# indicator_light.net
KiCad netlist of a schematic drawn in Altium Designer
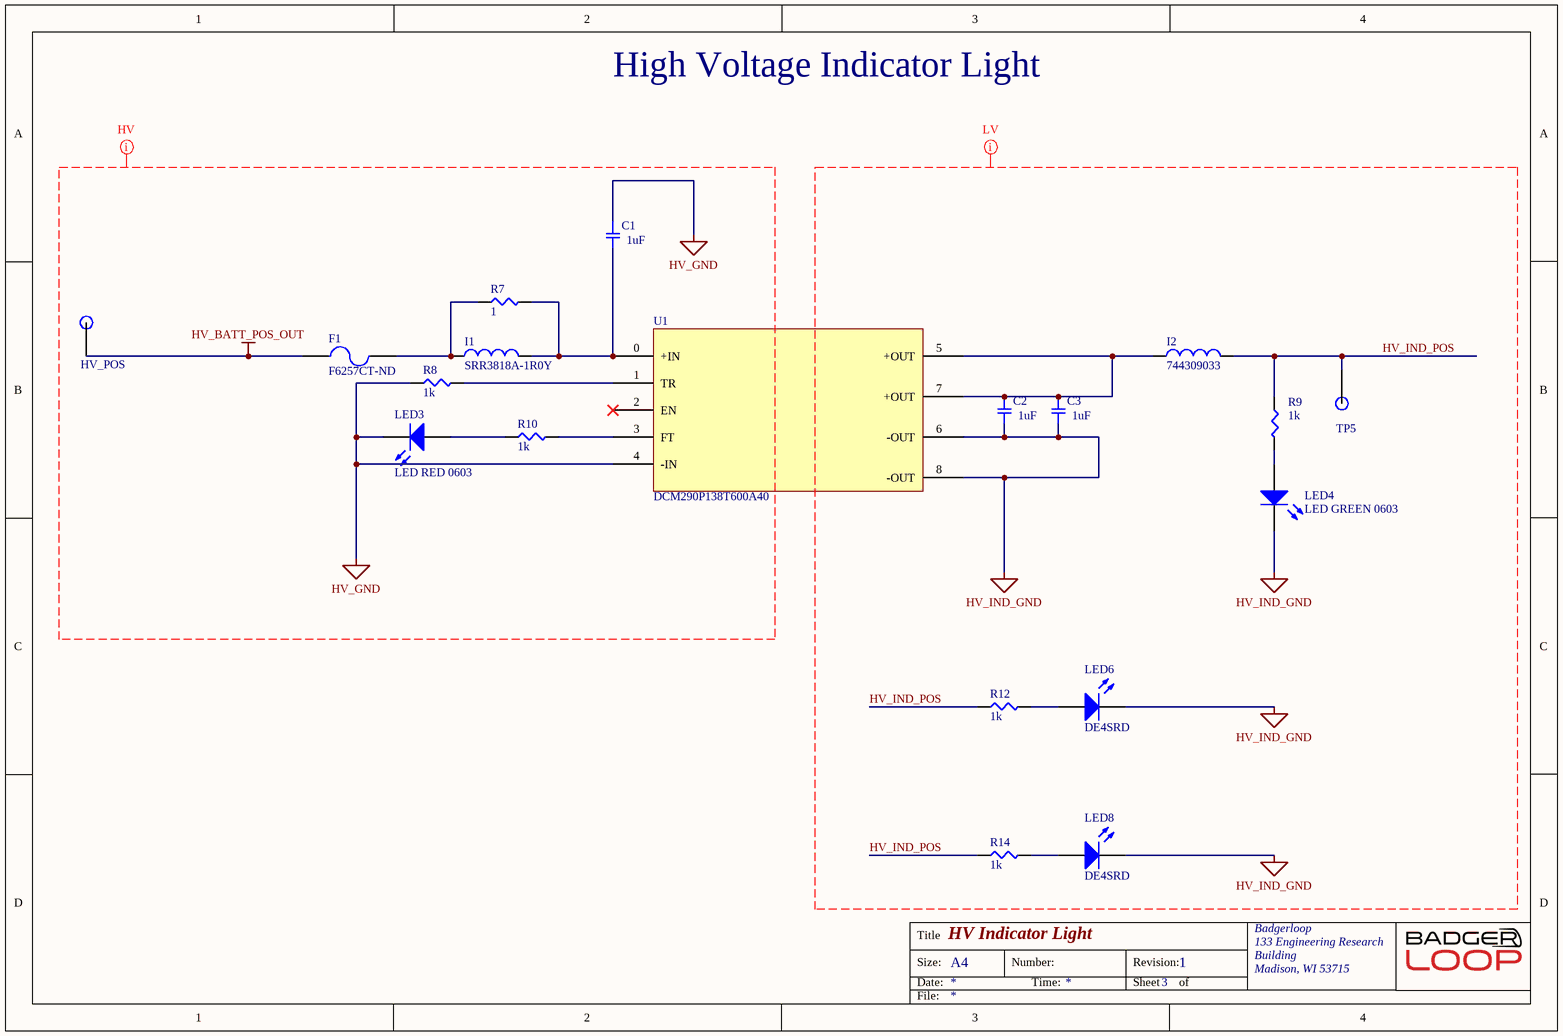
[diagram p0: indicator_light.SchDoc]

(export (version "E")
  (design (tool "Eeschema 10.0.6"))
  (components
    (comp (ref "C1")
      (value "CGA9P4X7T2W105K250KE_1")
      (footprint "CAPC5860X28N")
      (description "CAP CER 1UF 450V X7T 2220")
      (fields
        (field (name "MANUFACTURER") "TDK")
        (field (name "MANUFACTURER PART NUMBER") "CGA9P4X7T2W105K250KE")
        (field (name "CAPACITANCE") "1uF")
      )
      (libsource (lib "altium-import") (part "root_0_CGA9P4X7T2W105K250KE_1_"))
    )
    (comp (ref "C2")
      (value "CGA9P4X7T2W105K250KE_1")
      (footprint "CAPC5860X28N")
      (description "CAP CER 1UF 450V X7T 2220")
      (fields
        (field (name "MANUFACTURER") "TDK")
        (field (name "MANUFACTURER PART NUMBER") "CGA9P4X7T2W105K250KE")
        (field (name "CAPACITANCE") "1uF")
      )
      (libsource (lib "altium-import") (part "root_0_CGA9P4X7T2W105K250KE_1_"))
    )
    (comp (ref "C3")
      (value "CGA9P4X7T2W105K250KE_1")
      (footprint "CAPC5860X28N")
      (description "CAP CER 1UF 450V X7T 2220")
      (fields
        (field (name "MANUFACTURER") "TDK")
        (field (name "MANUFACTURER PART NUMBER") "CGA9P4X7T2W105K250KE")
        (field (name "CAPACITANCE") "1uF")
      )
      (libsource (lib "altium-import") (part "root_0_CGA9P4X7T2W105K250KE_1_"))
    )
    (comp (ref "F1")
      (value "F6257CT-ND")
      (footprint "FUSE BOARD MNT 500MA 350VAC/VDC")
      (description "FUSE BOARD MNT 500MA 350VAC/VDC")
      (fields (field (name "MANUFACTURER") "Littelfuse"))
      (libsource (lib "misc") (part "F6257CT-ND"))
    )
    (comp (ref "HV_POS")
      (value "TP")
      (footprint "Test Point")
      (description "SMD TEST POINT")
      (libsource (lib "misc") (part "TP"))
    )
    (comp (ref "I1")
      (value "SRR3818A-1R0Y")
      (footprint "INDM3838X18N")
      (description "FIXED IND 1UH 3.6A 37 MOHM SMD")
      (fields (field (name "MANUFACTURER") "Bourns Inc."))
      (libsource (lib "misc") (part "SRR3818A-1R0Y"))
    )
    (comp (ref "I2")
      (value "744309033")
      (footprint "INDM140130X90N")
      (description "FIXED IND 330NH 47.5A 0.165 MOHM")
      (fields (field (name "MANUFACTURER") "Wurth"))
      (libsource (lib "misc") (part "744309033"))
    )
    (comp (ref "LED3")
      (value "LED RED 0603")
      (footprint "LED 0603 RED")
      (description "Red 631nm LED Indication - Discrete 2V 0603 (1608 Metric)")
      (fields (field (name "MANUFACTURER") "Lite-On Inc."))
      (libsource (lib "misc") (part "LED RED 0603"))
    )
    (comp (ref "LED4")
      (value "LED GREEN 0603")
      (footprint "LED 0603 GREEN")
      (fields (field (name "MANUFACTURER") "Lite-On Inc."))
      (libsource (lib "misc") (part "LED GREEN 0603"))
    )
    (comp (ref "LED6")
      (value "DE4SRD")
      (footprint "DE4SRD")
      (description "LED Bars and Arrays Red 640nm 300mcd Diffused Light Bar")
      (fields (field (name "MANUFACTURER") "Kingbright"))
      (libsource (lib "shelby_temp") (part "DE4SRD"))
    )
    (comp (ref "LED8")
      (value "DE4SRD")
      (footprint "DE4SRD")
      (description "LED Bars and Arrays Red 640nm 300mcd Diffused Light Bar")
      (fields (field (name "MANUFACTURER") "Kingbright"))
      (libsource (lib "shelby_temp") (part "DE4SRD"))
    )
    (comp (ref "R7")
      (value "1")
      (footprint "SMD-0805-RES")
      (description "RES SMD 1 OHM 5% 1/3W 0805")
      (fields (field (name "PART NUMBER") "ERJ-6BQJ1R0V") (field (name "DIGI-KEY PART NUMBER") "P17527CT-ND"))
      (libsource (lib "resistors") (part "ERJ-6BQJ1R0V"))
    )
    (comp (ref "R8")
      (value "1k")
      (footprint "SMD-0805-RES")
      (description "RES SMD 1K OHM 1% 1/8W 0805")
      (fields
        (field (name "PART NUMBER") "ERJ-6ENF1001V")
        (field (name "DIGI-KEY PART NUMBER") "P1.00KCCT-ND")
      )
      (libsource (lib "resistors") (part "ERJ-6ENF1001V"))
    )
    (comp (ref "R9")
      (value "1k")
      (footprint "SMD-0805-RES")
      (description "RES SMD 1K OHM 1% 1/8W 0805")
      (fields
        (field (name "PART NUMBER") "ERJ-6ENF1001V")
        (field (name "DIGI-KEY PART NUMBER") "P1.00KCCT-ND")
      )
      (libsource (lib "resistors") (part "ERJ-6ENF1001V"))
    )
    (comp (ref "R10")
      (value "1k")
      (footprint "SMD-0805-RES")
      (description "RES SMD 1K OHM 1% 1/8W 0805")
      (fields
        (field (name "PART NUMBER") "ERJ-6ENF1001V")
        (field (name "DIGI-KEY PART NUMBER") "P1.00KCCT-ND")
      )
      (libsource (lib "resistors") (part "ERJ-6ENF1001V"))
    )
    (comp (ref "R12")
      (value "1k")
      (footprint "SMD-0805-RES")
      (description "RES SMD 1K OHM 1% 1/8W 0805")
      (fields
        (field (name "PART NUMBER") "ERJ-6ENF1001V")
        (field (name "DIGI-KEY PART NUMBER") "P1.00KCCT-ND")
      )
      (libsource (lib "resistors") (part "ERJ-6ENF1001V"))
    )
    (comp (ref "R14")
      (value "1k")
      (footprint "SMD-0805-RES")
      (description "RES SMD 1K OHM 1% 1/8W 0805")
      (fields
        (field (name "PART NUMBER") "ERJ-6ENF1001V")
        (field (name "DIGI-KEY PART NUMBER") "P1.00KCCT-ND")
      )
      (libsource (lib "resistors") (part "ERJ-6ENF1001V"))
    )
    (comp (ref "TP5")
      (value "TP")
      (footprint "Test Point")
      (description "SMD TEST POINT")
      (libsource (lib "misc") (part "TP"))
    )
    (comp (ref "U1")
      (value "DCM290P138T600A40")
      (footprint "DCM290y138x600A40")
      (description "DC DC CONVERTER 13.8V 600W")
      (fields (field (name "MANUFACTURER") "Vicor"))
      (libsource (lib "ic") (part "DCM290P138T600A40"))
    )
  )
  (nets
    (net (code "1") (name "/HV_IND_POS") (class "Default")
      (node (ref "I2") (pin "2") (pinfunction "2_2") (pintype "passive"))
      (node (ref "R12") (pin "1") (pinfunction "1_1") (pintype "passive"))
      (node (ref "R14") (pin "1") (pinfunction "1_1") (pintype "passive"))
      (node (ref "R9") (pin "1") (pinfunction "1_1") (pintype "passive"))
      (node (ref "TP5") (pin "1") (pinfunction "1_1") (pintype "passive"))
    )
    (net (code "2") (name "HV_BATT_POS_OUT") (class "Default")
      (node (ref "F1") (pin "1") (pinfunction "1_1") (pintype "passive"))
      (node (ref "HV_POS") (pin "1") (pinfunction "1_1") (pintype "passive"))
    )
    (net (code "3") (name "HV_GND") (class "Default")
      (node (ref "C1") (pin "1") (pinfunction "1_1") (pintype "passive"))
      (node (ref "LED3") (pin "2") (pinfunction "K_2") (pintype "passive"))
      (node (ref "R8") (pin "1") (pinfunction "1_1") (pintype "passive"))
      (node (ref "U1") (pin "4") (pinfunction "-IN_4") (pintype "passive"))
    )
    (net (code "4") (name "HV_IND_GND") (class "Default")
      (node (ref "C2") (pin "2") (pinfunction "2_2") (pintype "passive"))
      (node (ref "C3") (pin "2") (pinfunction "2_2") (pintype "passive"))
      (node (ref "LED4") (pin "2") (pinfunction "K_2") (pintype "passive"))
      (node (ref "LED6") (pin "2") (pinfunction "K_2") (pintype "passive"))
      (node (ref "LED8") (pin "2") (pinfunction "K_2") (pintype "passive"))
      (node (ref "U1") (pin "6") (pinfunction "-OUT_6") (pintype "passive"))
      (node (ref "U1") (pin "8") (pinfunction "-OUT_8") (pintype "passive"))
    )
    (net (code "5") (name "Net-(C2-Pad1)") (class "Default")
      (node (ref "C2") (pin "1") (pinfunction "1_1") (pintype "passive"))
      (node (ref "C3") (pin "1") (pinfunction "1_1") (pintype "passive"))
      (node (ref "I2") (pin "1") (pinfunction "1_1") (pintype "passive"))
      (node (ref "U1") (pin "5") (pinfunction "+OUT_5") (pintype "passive"))
      (node (ref "U1") (pin "7") (pinfunction "+OUT_7") (pintype "passive"))
    )
    (net (code "6") (name "Net-(F1-Pad2)") (class "Default")
      (node (ref "F1") (pin "2") (pinfunction "2_2") (pintype "passive"))
      (node (ref "I1") (pin "1") (pinfunction "1_1") (pintype "passive"))
      (node (ref "R7") (pin "1") (pinfunction "1_1") (pintype "passive"))
    )
    (net (code "7") (name "Net-(LED3-A)") (class "Default")
      (node (ref "LED3") (pin "1") (pinfunction "A_1") (pintype "passive"))
      (node (ref "R10") (pin "1") (pinfunction "1_1") (pintype "passive"))
    )
    (net (code "8") (name "Net-(LED4-A)") (class "Default")
      (node (ref "LED4") (pin "1") (pinfunction "A_1") (pintype "passive"))
      (node (ref "R9") (pin "2") (pinfunction "2_2") (pintype "passive"))
    )
    (net (code "9") (name "Net-(LED6-A)") (class "Default")
      (node (ref "LED6") (pin "1") (pinfunction "A_1") (pintype "passive"))
      (node (ref "R12") (pin "2") (pinfunction "2_2") (pintype "passive"))
    )
    (net (code "10") (name "Net-(LED8-A)") (class "Default")
      (node (ref "LED8") (pin "1") (pinfunction "A_1") (pintype "passive"))
      (node (ref "R14") (pin "2") (pinfunction "2_2") (pintype "passive"))
    )
    (net (code "11") (name "Net-(U1-+IN)") (class "Default")
      (node (ref "C1") (pin "2") (pinfunction "2_2") (pintype "passive"))
      (node (ref "I1") (pin "2") (pinfunction "2_2") (pintype "passive"))
      (node (ref "R7") (pin "2") (pinfunction "2_2") (pintype "passive"))
      (node (ref "U1") (pin "0") (pinfunction "+IN_0") (pintype "passive"))
    )
    (net (code "12") (name "Net-(U1-FT)") (class "Default")
      (node (ref "R10") (pin "2") (pinfunction "2_2") (pintype "passive"))
      (node (ref "U1") (pin "3") (pinfunction "FT_3") (pintype "passive"))
    )
    (net (code "13") (name "Net-(U1-TR)") (class "Default")
      (node (ref "R8") (pin "2") (pinfunction "2_2") (pintype "passive"))
      (node (ref "U1") (pin "1") (pinfunction "TR_1") (pintype "passive"))
    )
    (net (code "14") (name "unconnected-(U1-EN-Pad2)") (class "Default")
      (node (ref "U1") (pin "2") (pinfunction "EN_2") (pintype "passive+no_connect"))
    )
  )
)
